# MotorDriverSchm.net
KiCad netlist of a schematic drawn in Altium Designer
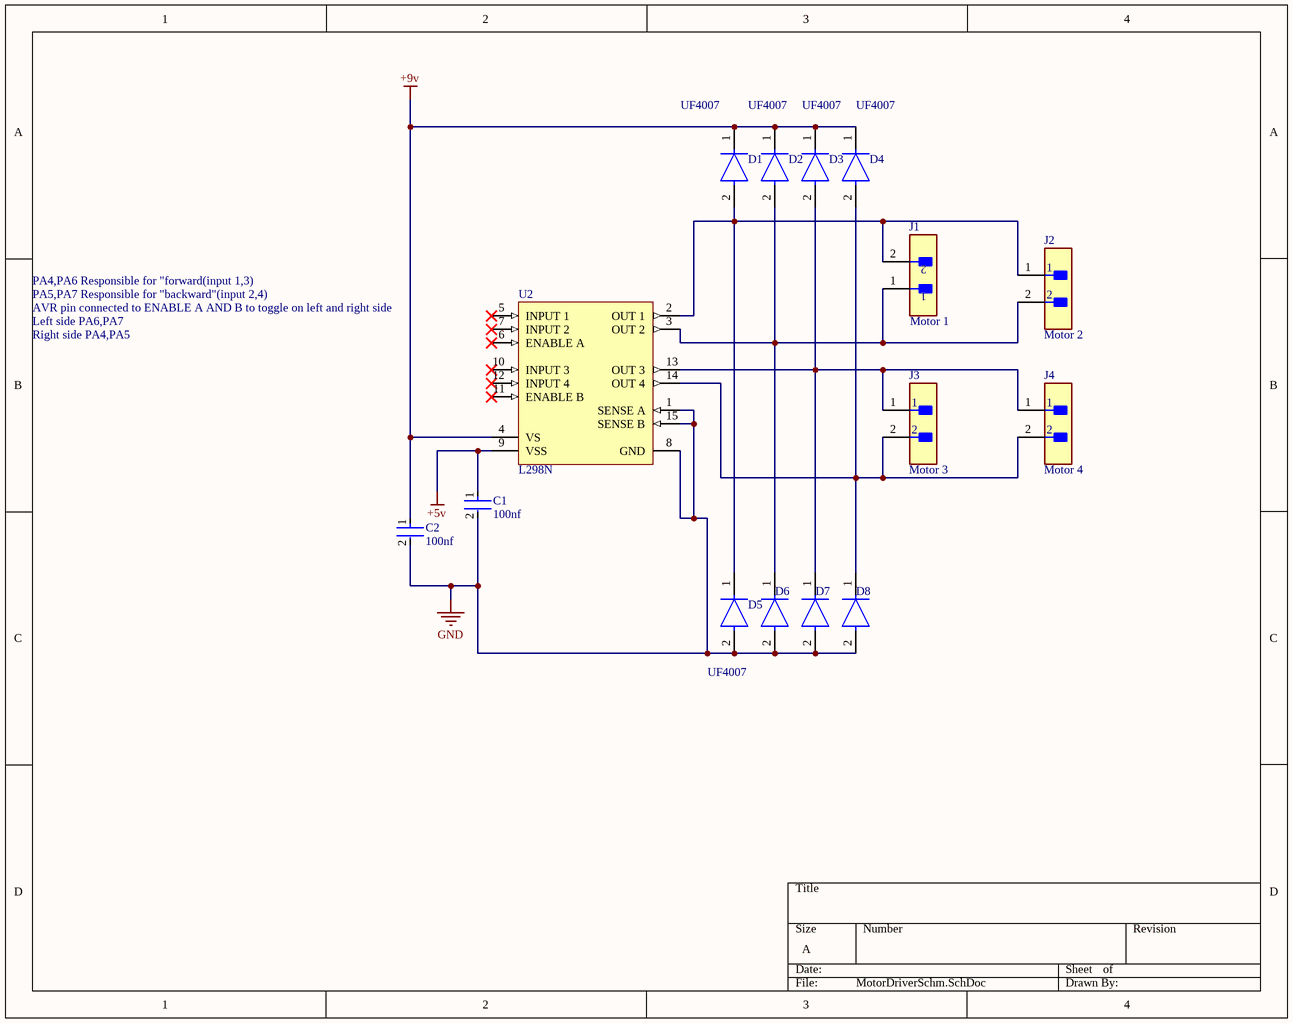
[diagram p0: MotorDriverSchm.SchDoc]

(export (version "E")
  (design (tool "Eeschema 10.0.6"))
  (components
    (comp (ref "C1")
      (value "100nf")
      (footprint "FP-C0402-BB-MFG")
      (description "C0402 0.10 μF X5R 10.00% 10 V")
      (fields (field (name "MANUFACTURER") "Kemet"))
      (libsource (lib "Altium Content Vault") (part "b4654b650e69147ec39a6b967a45e02"))
    )
    (comp (ref "C2")
      (value "100nf")
      (footprint "FP-C0402-BB-MFG")
      (description "C0402 0.10 μF X5R 10.00% 10 V")
      (fields (field (name "MANUFACTURER") "Kemet"))
      (libsource (lib "Altium Content Vault") (part "b4654b650e69147ec39a6b967a45e02"))
    )
    (comp (ref "D1")
      (value "UF4007")
      (footprint "FP-UF4007-MFG")
      (description "DIODE GEN PURP 1KV 1A DO204AL")
      (fields
        (field (name "MANUFACTURER") "Vishay")
        (field (name "OCTOPART") "https://octopart.com/uf4007-e3%2F54-vishay-42333894")
      )
      (libsource (lib "Altium Content Vault") (part "d7152d700b627762746794eb795d46e"))
    )
    (comp (ref "D2")
      (value "UF4007")
      (footprint "FP-UF4007-MFG")
      (description "DIODE GEN PURP 1KV 1A DO204AL")
      (fields
        (field (name "MANUFACTURER") "Vishay")
        (field (name "OCTOPART") "https://octopart.com/uf4007-e3%2F54-vishay-42333894")
      )
      (libsource (lib "Altium Content Vault") (part "d7152d700b627762746794eb795d46e"))
    )
    (comp (ref "D3")
      (value "UF4007")
      (footprint "FP-UF4007-MFG")
      (description "DIODE GEN PURP 1KV 1A DO204AL")
      (fields
        (field (name "MANUFACTURER") "Vishay")
        (field (name "OCTOPART") "https://octopart.com/uf4007-e3%2F54-vishay-42333894")
      )
      (libsource (lib "Altium Content Vault") (part "d7152d700b627762746794eb795d46e"))
    )
    (comp (ref "D4")
      (value "UF4007")
      (footprint "FP-UF4007-MFG")
      (description "DIODE GEN PURP 1KV 1A DO204AL")
      (fields
        (field (name "MANUFACTURER") "Vishay")
        (field (name "OCTOPART") "https://octopart.com/uf4007-e3%2F54-vishay-42333894")
      )
      (libsource (lib "Altium Content Vault") (part "d7152d700b627762746794eb795d46e"))
    )
    (comp (ref "D5")
      (value "UF4007")
      (footprint "FP-UF4007-MFG")
      (description "DIODE GEN PURP 1KV 1A DO204AL")
      (fields
        (field (name "MANUFACTURER") "Vishay")
        (field (name "OCTOPART") "https://octopart.com/uf4007-e3%2F54-vishay-42333894")
      )
      (libsource (lib "Altium Content Vault") (part "d7152d700b627762746794eb795d46e"))
    )
    (comp (ref "D6")
      (value "~")
      (footprint "FP-UF4007-MFG")
      (description "DIODE GEN PURP 1KV 1A DO204AL")
      (fields
        (field (name "MANUFACTURER") "Vishay")
        (field (name "OCTOPART") "https://octopart.com/uf4007-e3%2F54-vishay-42333894")
      )
      (libsource (lib "Altium Content Vault") (part "d7152d700b627762746794eb795d46e"))
    )
    (comp (ref "D7")
      (value "~")
      (footprint "FP-UF4007-MFG")
      (description "DIODE GEN PURP 1KV 1A DO204AL")
      (fields
        (field (name "MANUFACTURER") "Vishay")
        (field (name "OCTOPART") "https://octopart.com/uf4007-e3%2F54-vishay-42333894")
      )
      (libsource (lib "Altium Content Vault") (part "d7152d700b627762746794eb795d46e"))
    )
    (comp (ref "D8")
      (value "~")
      (footprint "FP-UF4007-MFG")
      (description "DIODE GEN PURP 1KV 1A DO204AL")
      (fields
        (field (name "MANUFACTURER") "Vishay")
        (field (name "OCTOPART") "https://octopart.com/uf4007-e3%2F54-vishay-42333894")
      )
      (libsource (lib "Altium Content Vault") (part "d7152d700b627762746794eb795d46e"))
    )
    (comp (ref "J1")
      (value "Motor 1")
      (footprint "FP-M20-9990246-MFG")
      (description "Connector Header Through Hole 2 position 0.100\" (2.54mm)")
      (fields (field (name "OCTOPART") "https://octopart.com/m20-9990246-harwin-2590635"))
      (libsource (lib "Altium Content Vault") (part "3bc925449376181038e59eaffc5286c"))
    )
    (comp (ref "J2")
      (value "Motor 2")
      (footprint "FP-M20-9990246-MFG")
      (description "Connector Header Through Hole 2 position 0.100\" (2.54mm)")
      (fields (field (name "OCTOPART") "https://octopart.com/m20-9990246-harwin-2590635"))
      (libsource (lib "") (part "3bc925449376181038e59eaffc5286c_1"))
    )
    (comp (ref "J3")
      (value "Motor 3")
      (footprint "FP-M20-9990246-MFG")
      (description "Connector Header Through Hole 2 position 0.100\" (2.54mm)")
      (fields (field (name "OCTOPART") "https://octopart.com/m20-9990246-harwin-2590635"))
      (libsource (lib "") (part "3bc925449376181038e59eaffc5286c_1"))
    )
    (comp (ref "J4")
      (value "Motor 4")
      (footprint "FP-M20-9990246-MFG")
      (description "Connector Header Through Hole 2 position 0.100\" (2.54mm)")
      (fields (field (name "OCTOPART") "https://octopart.com/m20-9990246-harwin-2590635"))
      (libsource (lib "") (part "3bc925449376181038e59eaffc5286c_1"))
    )
    (comp (ref "U2")
      (value "L298N")
      (footprint "STM-FM-15")
      (description "Dual Full-Bridge Driver, 4.8 to 46 V, -40 to 150 degC, 15-Pin FM (MW 15L), RoHS, Tube")
      (fields (field (name "MANUFACTURER") "STMicroelectronics") (field (name "PARTNUMBER") "L298"))
      (libsource (lib "Altium Content Vault") (part "STM-L298-15"))
    )
  )
  (nets
    (net (code "1") (name "+5v") (class "Default")
      (node (ref "C1") (pin "1") (pinfunction "1_1") (pintype "passive"))
      (node (ref "U2") (pin "9") (pinfunction "VSS_9") (pintype "power_in"))
    )
    (net (code "2") (name "+9v") (class "Default")
      (node (ref "C2") (pin "1") (pinfunction "1_1") (pintype "passive"))
      (node (ref "D1") (pin "1") (pinfunction "C_1") (pintype "passive"))
      (node (ref "D2") (pin "1") (pinfunction "C_1") (pintype "passive"))
      (node (ref "D3") (pin "1") (pinfunction "C_1") (pintype "passive"))
      (node (ref "D4") (pin "1") (pinfunction "C_1") (pintype "passive"))
      (node (ref "U2") (pin "4") (pinfunction "VS_4") (pintype "power_in"))
    )
    (net (code "3") (name "GND") (class "Default")
      (node (ref "C1") (pin "2") (pinfunction "2_2") (pintype "passive"))
      (node (ref "C2") (pin "2") (pinfunction "2_2") (pintype "passive"))
      (node (ref "D5") (pin "2") (pinfunction "A_2") (pintype "passive"))
      (node (ref "D6") (pin "2") (pinfunction "A_2") (pintype "passive"))
      (node (ref "D7") (pin "2") (pinfunction "A_2") (pintype "passive"))
      (node (ref "D8") (pin "2") (pinfunction "A_2") (pintype "passive"))
      (node (ref "U2") (pin "1") (pinfunction "SENSE_A_1") (pintype "input"))
      (node (ref "U2") (pin "15") (pinfunction "SENSE_B_15") (pintype "input"))
      (node (ref "U2") (pin "8") (pinfunction "GND_8") (pintype "power_in"))
    )
    (net (code "4") (name "Net-(D1-A)") (class "Default")
      (node (ref "D1") (pin "2") (pinfunction "A_2") (pintype "passive"))
      (node (ref "D5") (pin "1") (pinfunction "C_1") (pintype "passive"))
      (node (ref "J1") (pin "2") (pinfunction "2_2") (pintype "passive"))
      (node (ref "J2") (pin "1") (pinfunction "1_1") (pintype "passive"))
      (node (ref "U2") (pin "2") (pinfunction "OUT_1_2") (pintype "output"))
    )
    (net (code "5") (name "Net-(D2-A)") (class "Default")
      (node (ref "D2") (pin "2") (pinfunction "A_2") (pintype "passive"))
      (node (ref "D6") (pin "1") (pinfunction "C_1") (pintype "passive"))
      (node (ref "J1") (pin "1") (pinfunction "1_1") (pintype "passive"))
      (node (ref "J2") (pin "2") (pinfunction "2_2") (pintype "passive"))
      (node (ref "U2") (pin "3") (pinfunction "OUT_2_3") (pintype "output"))
    )
    (net (code "6") (name "Net-(D3-A)") (class "Default")
      (node (ref "D3") (pin "2") (pinfunction "A_2") (pintype "passive"))
      (node (ref "D7") (pin "1") (pinfunction "C_1") (pintype "passive"))
      (node (ref "J3") (pin "1") (pinfunction "1_1") (pintype "passive"))
      (node (ref "J4") (pin "1") (pinfunction "1_1") (pintype "passive"))
      (node (ref "U2") (pin "13") (pinfunction "OUT_3_13") (pintype "output"))
    )
    (net (code "7") (name "Net-(D4-A)") (class "Default")
      (node (ref "D4") (pin "2") (pinfunction "A_2") (pintype "passive"))
      (node (ref "D8") (pin "1") (pinfunction "C_1") (pintype "passive"))
      (node (ref "J3") (pin "2") (pinfunction "2_2") (pintype "passive"))
      (node (ref "J4") (pin "2") (pinfunction "2_2") (pintype "passive"))
      (node (ref "U2") (pin "14") (pinfunction "OUT_4_14") (pintype "output"))
    )
    (net (code "8") (name "unconnected-(U2-ENABLE_A-Pad6)") (class "Default")
      (node (ref "U2") (pin "6") (pinfunction "ENABLE_A_6") (pintype "input+no_connect"))
    )
    (net (code "9") (name "unconnected-(U2-ENABLE_B-Pad11)") (class "Default")
      (node (ref "U2") (pin "11") (pinfunction "ENABLE_B_11") (pintype "input+no_connect"))
    )
    (net (code "10") (name "unconnected-(U2-INPUT_1-Pad5)") (class "Default")
      (node (ref "U2") (pin "5") (pinfunction "INPUT_1_5") (pintype "input+no_connect"))
    )
    (net (code "11") (name "unconnected-(U2-INPUT_2-Pad7)") (class "Default")
      (node (ref "U2") (pin "7") (pinfunction "INPUT_2_7") (pintype "input+no_connect"))
    )
    (net (code "12") (name "unconnected-(U2-INPUT_3-Pad10)") (class "Default")
      (node (ref "U2") (pin "10") (pinfunction "INPUT_3_10") (pintype "input+no_connect"))
    )
    (net (code "13") (name "unconnected-(U2-INPUT_4-Pad12)") (class "Default")
      (node (ref "U2") (pin "12") (pinfunction "INPUT_4_12") (pintype "input+no_connect"))
    )
  )
)
